# ciot.net
KiCad netlist of a schematic drawn in EAGLE
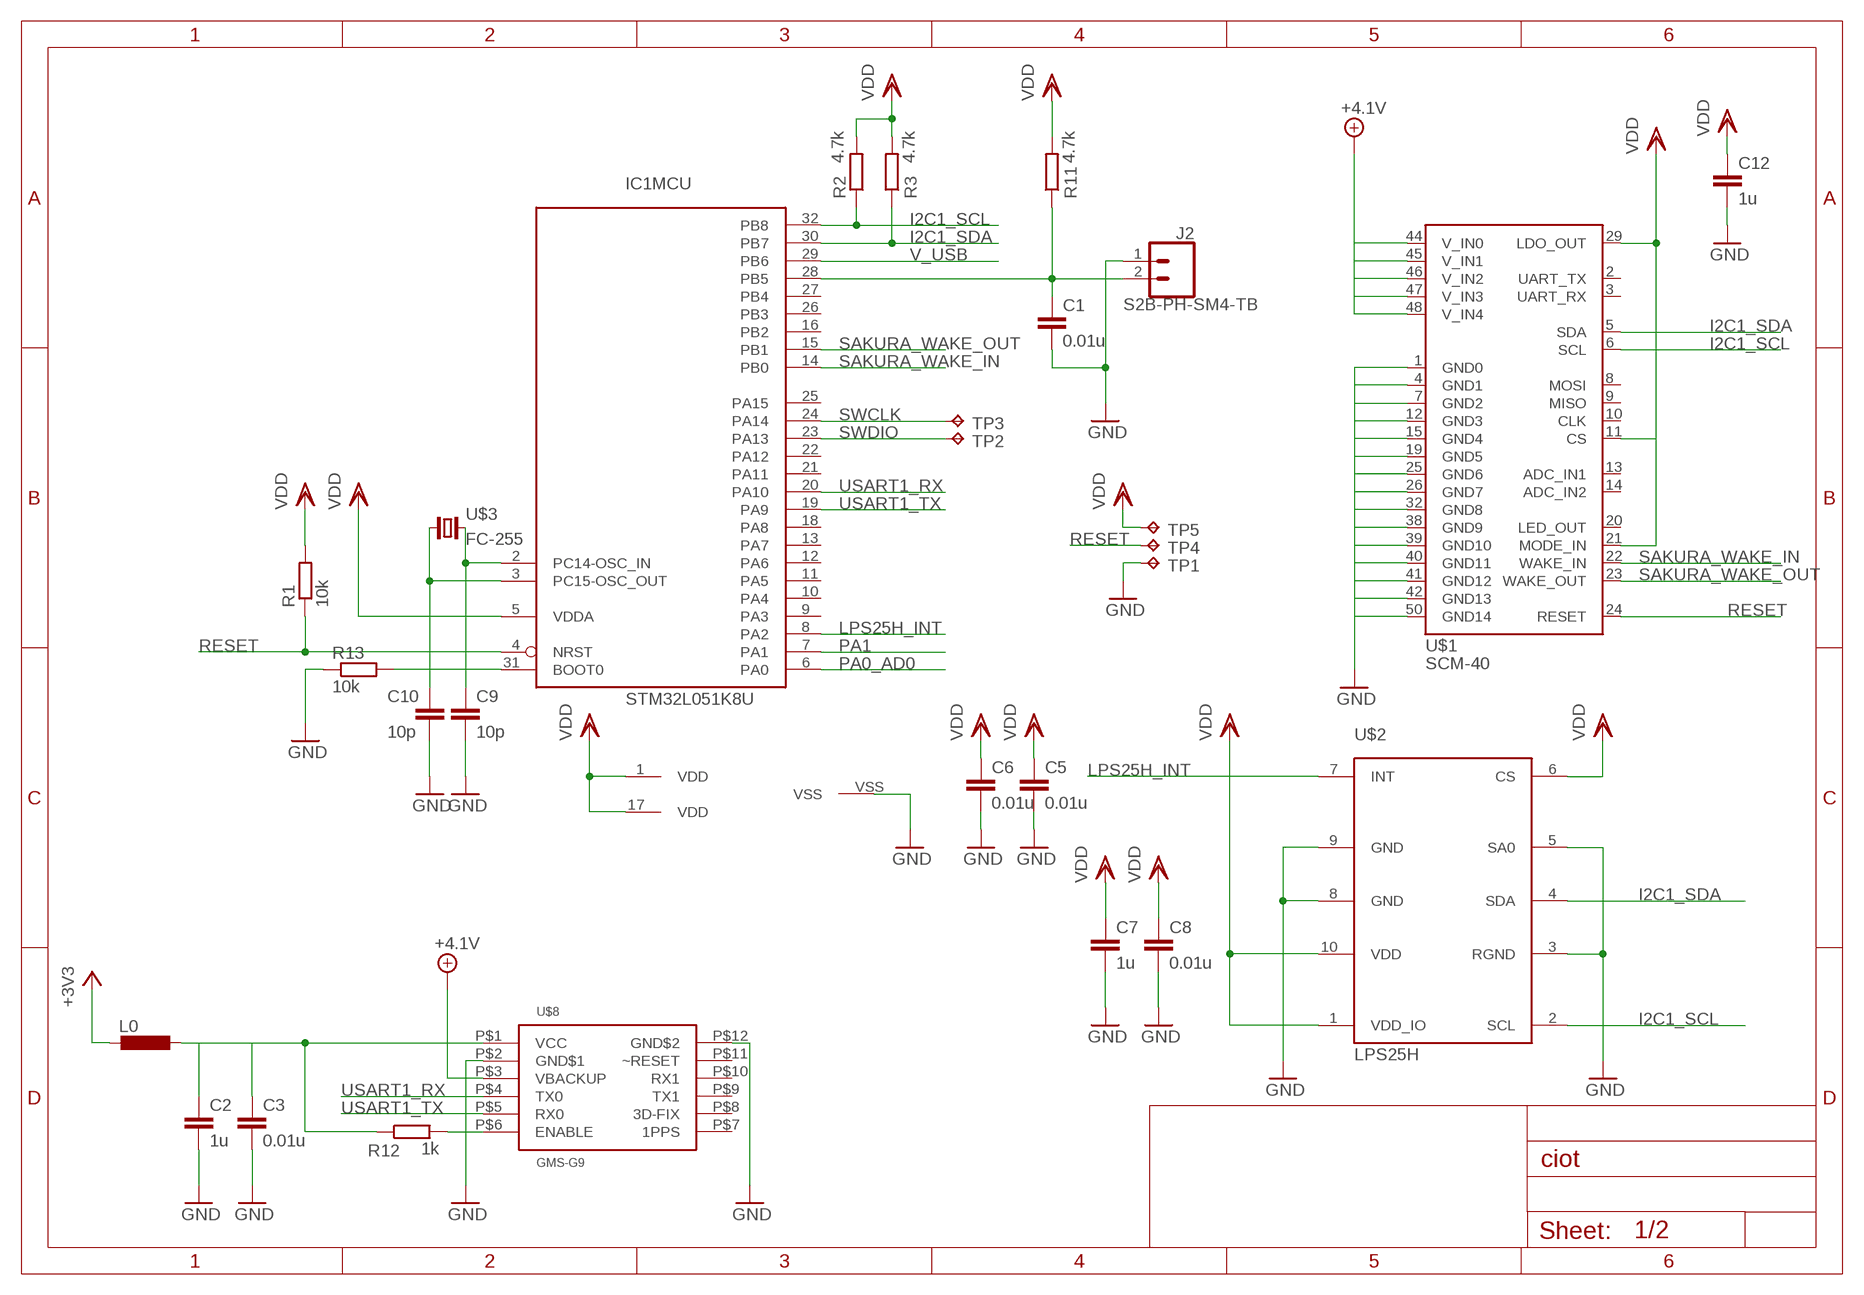
[diagram p0: schematic, sheet 1]
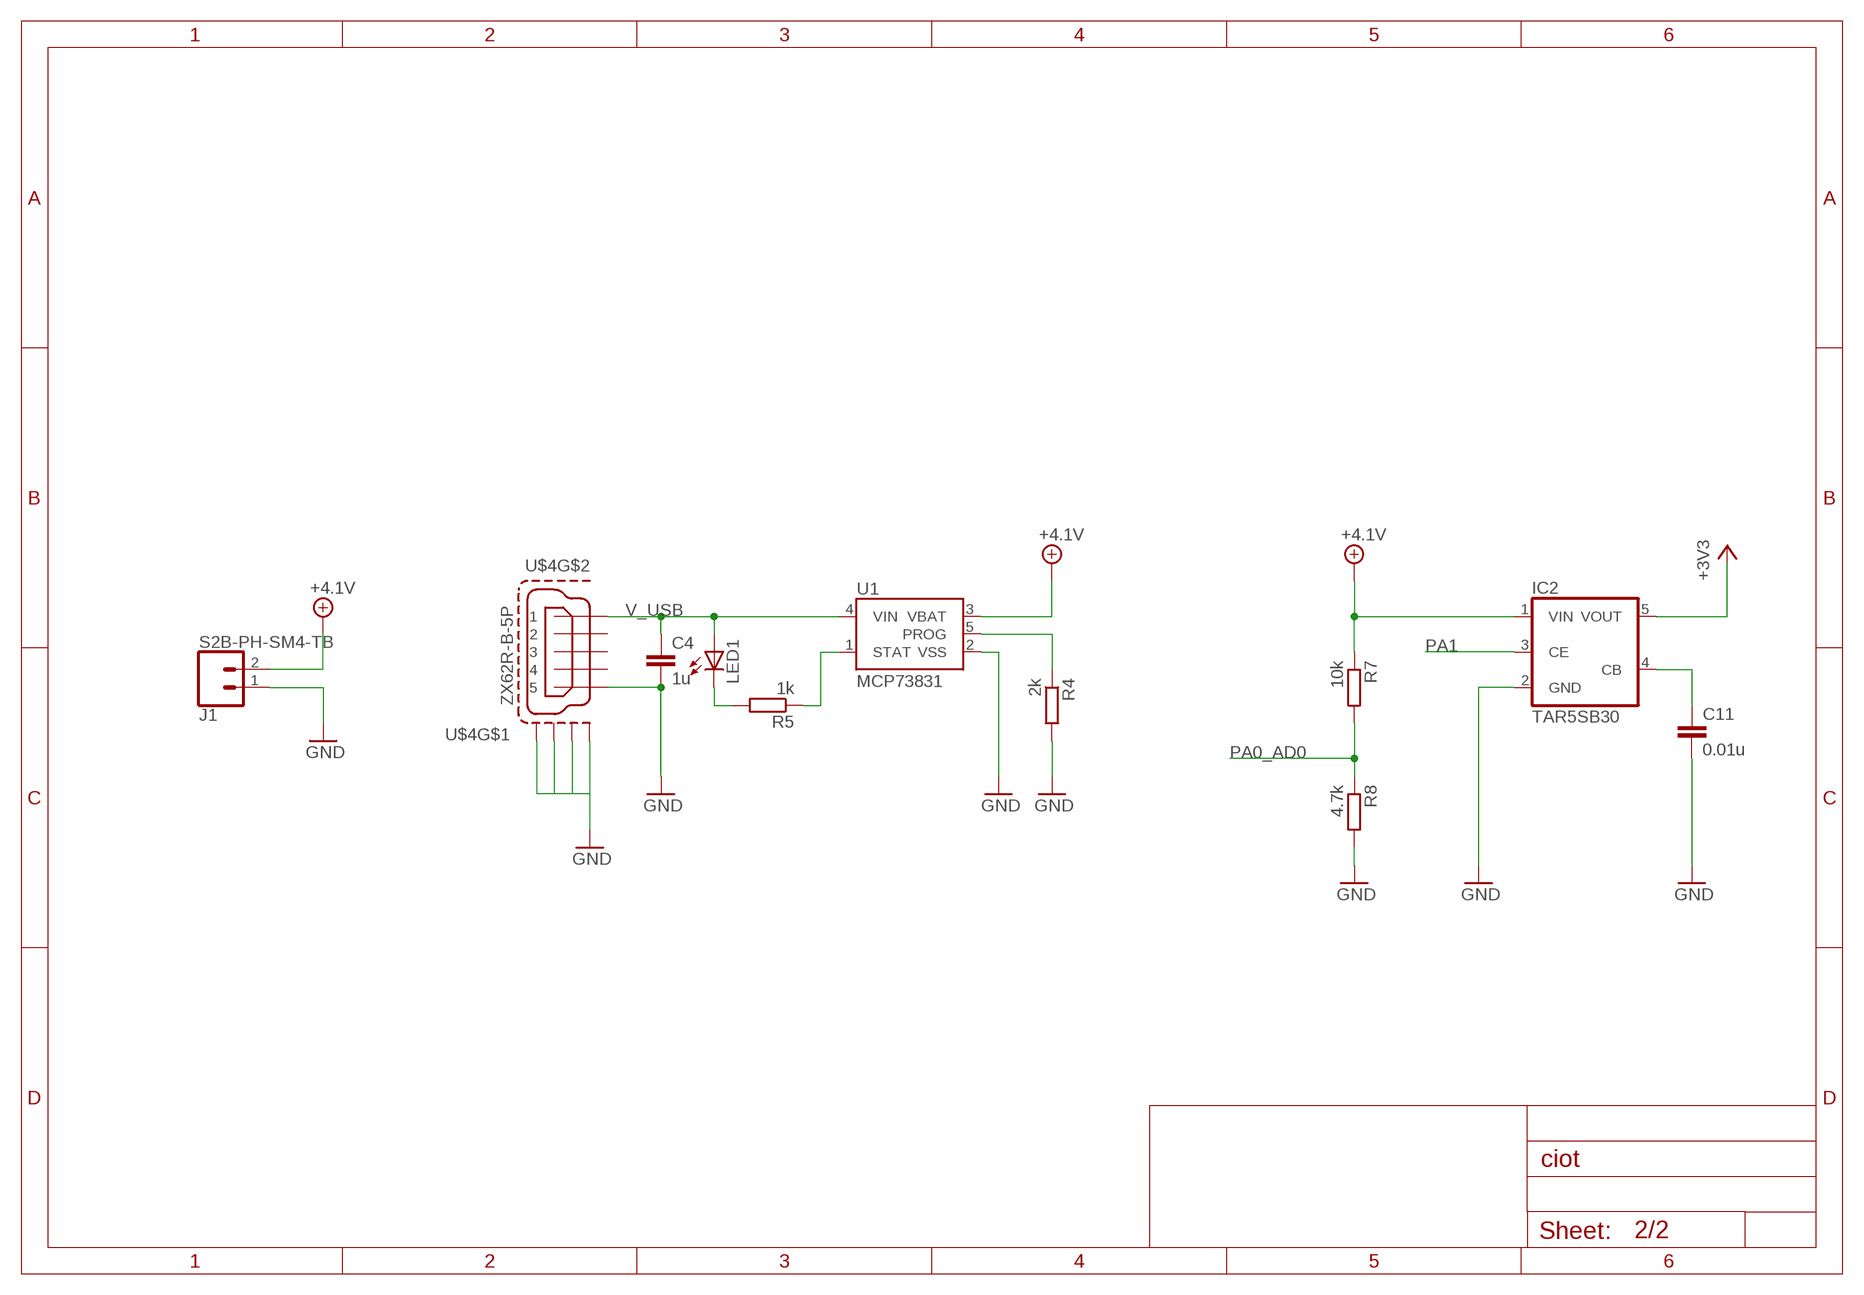
[diagram p1: schematic, sheet 2]

(export (version "E")
  (design (tool "Eeschema 10.0.6"))
  (components
    (comp (ref "C1")
      (value "0.01u")
      (footprint "eagle-import:C0603K")
      (libsource (lib "eagle-import") (part "C-EUC0603K"))
    )
    (comp (ref "C2")
      (value "1u")
      (footprint "eagle-import:C0603K")
      (libsource (lib "eagle-import") (part "C-EUC0603K"))
    )
    (comp (ref "C3")
      (value "0.01u")
      (footprint "eagle-import:C0603K")
      (libsource (lib "eagle-import") (part "C-EUC0603K"))
    )
    (comp (ref "C5")
      (value "0.01u")
      (footprint "eagle-import:C0603K")
      (libsource (lib "eagle-import") (part "C-EUC0603K"))
    )
    (comp (ref "C6")
      (value "0.01u")
      (footprint "eagle-import:C0603K")
      (libsource (lib "eagle-import") (part "C-EUC0603K"))
    )
    (comp (ref "C7")
      (value "1u")
      (footprint "eagle-import:C0603K")
      (libsource (lib "eagle-import") (part "C-EUC0603K"))
    )
    (comp (ref "C8")
      (value "0.01u")
      (footprint "eagle-import:C0603K")
      (libsource (lib "eagle-import") (part "C-EUC0603K"))
    )
    (comp (ref "C9")
      (value "10p")
      (footprint "eagle-import:C0603K")
      (libsource (lib "eagle-import") (part "C-EUC0603K"))
    )
    (comp (ref "C10")
      (value "10p")
      (footprint "eagle-import:C0603K")
      (libsource (lib "eagle-import") (part "C-EUC0603K"))
    )
    (comp (ref "C12")
      (value "1u")
      (footprint "eagle-import:C0603K")
      (libsource (lib "eagle-import") (part "C-EUC0603K"))
    )
    (comp (ref "IC1")
      (value "STM32L051K8U")
      (footprint "eagle-import:UFQFPN32")
      (libsource (lib "eagle-import") (part "STM32L051KU8"))
    )
    (comp (ref "J2")
      (value "S2B-PH-SM4-TB")
      (footprint "eagle-import:JST-2-SMD")
      (libsource (lib "eagle-import") (part "CONN_02-JST-2MM-SMT"))
    )
    (comp (ref "L0")
      (value "L-EUL2012C")
      (footprint "eagle-import:L2012C")
      (libsource (lib "eagle-import") (part "L-EUL2012C"))
    )
    (comp (ref "R1")
      (value "10k")
      (footprint "eagle-import:R0603")
      (libsource (lib "eagle-import") (part "R-EU_R0603"))
    )
    (comp (ref "R2")
      (value "4.7k")
      (footprint "eagle-import:R0603")
      (libsource (lib "eagle-import") (part "R-EU_R0603"))
    )
    (comp (ref "R3")
      (value "4.7k")
      (footprint "eagle-import:R0603")
      (libsource (lib "eagle-import") (part "R-EU_R0603"))
    )
    (comp (ref "R11")
      (value "4.7k")
      (footprint "eagle-import:R0603")
      (libsource (lib "eagle-import") (part "R-EU_R0603"))
    )
    (comp (ref "R12")
      (value "1k")
      (footprint "eagle-import:R0603")
      (libsource (lib "eagle-import") (part "R-EU_R0603"))
    )
    (comp (ref "R13")
      (value "10k")
      (footprint "eagle-import:R0603")
      (libsource (lib "eagle-import") (part "R-EU_R0603"))
    )
    (comp (ref "TP1")
      (value "TPB1,27")
      (footprint "eagle-import:B1,27")
      (libsource (lib "eagle-import") (part "TPB1,27"))
    )
    (comp (ref "TP2")
      (value "TPB1,27")
      (footprint "eagle-import:B1,27")
      (libsource (lib "eagle-import") (part "TPB1,27"))
    )
    (comp (ref "TP3")
      (value "TPB1,27")
      (footprint "eagle-import:B1,27")
      (libsource (lib "eagle-import") (part "TPB1,27"))
    )
    (comp (ref "TP4")
      (value "TPB1,27")
      (footprint "eagle-import:B1,27")
      (libsource (lib "eagle-import") (part "TPB1,27"))
    )
    (comp (ref "TP5")
      (value "TPB1,27")
      (footprint "eagle-import:B1,27")
      (libsource (lib "eagle-import") (part "TPB1,27"))
    )
    (comp (ref "U$1")
      (value "SCM-40")
      (footprint "eagle-import:SCM-DF40-50DS")
      (libsource (lib "eagle-import") (part "SCM-40"))
    )
    (comp (ref "U$2")
      (value "LPS25H")
      (footprint "eagle-import:LPS25H")
      (libsource (lib "eagle-import") (part "LPS25H"))
    )
    (comp (ref "U$3")
      (value "FC-255")
      (footprint "eagle-import:FC-255")
      (libsource (lib "eagle-import") (part "FC-255"))
    )
    (comp (ref "U$8")
      (value "GMS-G9")
      (footprint "eagle-import:GMS-G9")
      (libsource (lib "eagle-import") (part "GMS-G9"))
    )
    (comp (ref "C4")
      (value "1u")
      (footprint "eagle-import:C0603K")
      (libsource (lib "eagle-import") (part "C-EUC0603K"))
    )
    (comp (ref "C11")
      (value "0.01u")
      (footprint "eagle-import:C0603K")
      (libsource (lib "eagle-import") (part "C-EUC0603K"))
    )
    (comp (ref "IC2")
      (value "TAR5SB30")
      (footprint "eagle-import:SOT25")
      (libsource (lib "eagle-import") (part "TS520530"))
    )
    (comp (ref "J1")
      (value "S2B-PH-SM4-TB")
      (footprint "eagle-import:JST-2-SMD")
      (libsource (lib "eagle-import") (part "CONN_02-JST-2MM-SMT"))
    )
    (comp (ref "LED1")
      (value "LEDCHIPLED_0603")
      (footprint "eagle-import:CHIPLED_0603")
      (libsource (lib "eagle-import") (part "LEDCHIPLED_0603"))
    )
    (comp (ref "R4")
      (value "2k")
      (footprint "eagle-import:R0603")
      (libsource (lib "eagle-import") (part "R-EU_R0603"))
    )
    (comp (ref "R5")
      (value "1k")
      (footprint "eagle-import:R0603")
      (libsource (lib "eagle-import") (part "R-EU_R0603"))
    )
    (comp (ref "R7")
      (value "10k")
      (footprint "eagle-import:R0603")
      (libsource (lib "eagle-import") (part "R-EU_R0603"))
    )
    (comp (ref "R8")
      (value "4.7k")
      (footprint "eagle-import:R0603")
      (libsource (lib "eagle-import") (part "R-EU_R0603"))
    )
    (comp (ref "U$4")
      (value "ZX62R-B-5P")
      (footprint "eagle-import:ZX62R-B-5P")
      (libsource (lib "eagle-import") (part "MICRO-USB-SHIELD-ZX62R-B-5P"))
    )
    (comp (ref "U1")
      (value "MCP73831")
      (footprint "eagle-import:SOT23-5")
      (libsource (lib "eagle-import") (part "MCP73831"))
    )
  )
  (nets
    (net (code "1") (name "+3V3") (class "Default")
      (node (ref "IC2") (pin "5") (pinfunction "VOUT_5") (pintype "passive"))
      (node (ref "L0") (pin "2") (pinfunction "2_2") (pintype "passive"))
    )
    (net (code "2") (name "+4.1V") (class "Default")
      (node (ref "IC2") (pin "1") (pinfunction "VIN_1") (pintype "input"))
      (node (ref "J1") (pin "2") (pinfunction "1_2") (pintype "passive"))
      (node (ref "R7") (pin "1") (pinfunction "1_1") (pintype "passive"))
      (node (ref "U$1") (pin "44") (pinfunction "V_IN0_44") (pintype "power_in"))
      (node (ref "U$1") (pin "45") (pinfunction "V_IN1_45") (pintype "power_in"))
      (node (ref "U$1") (pin "46") (pinfunction "V_IN2_46") (pintype "power_in"))
      (node (ref "U$1") (pin "47") (pinfunction "V_IN3_47") (pintype "power_in"))
      (node (ref "U$1") (pin "48") (pinfunction "V_IN4_48") (pintype "power_in"))
      (node (ref "U$8") (pin "P$3") (pinfunction "VBACKUP_P$3") (pintype "bidirectional"))
      (node (ref "U1") (pin "3") (pinfunction "VBAT_3") (pintype "power_in"))
    )
    (net (code "3") (name "GND") (class "Default")
      (node (ref "C1") (pin "2") (pinfunction "2_2") (pintype "passive"))
      (node (ref "C10") (pin "2") (pinfunction "2_2") (pintype "passive"))
      (node (ref "C11") (pin "2") (pinfunction "2_2") (pintype "passive"))
      (node (ref "C12") (pin "2") (pinfunction "2_2") (pintype "passive"))
      (node (ref "C2") (pin "2") (pinfunction "2_2") (pintype "passive"))
      (node (ref "C3") (pin "2") (pinfunction "2_2") (pintype "passive"))
      (node (ref "C4") (pin "2") (pinfunction "2_2") (pintype "passive"))
      (node (ref "C5") (pin "2") (pinfunction "2_2") (pintype "passive"))
      (node (ref "C6") (pin "2") (pinfunction "2_2") (pintype "passive"))
      (node (ref "C7") (pin "2") (pinfunction "2_2") (pintype "passive"))
      (node (ref "C8") (pin "2") (pinfunction "2_2") (pintype "passive"))
      (node (ref "C9") (pin "2") (pinfunction "2_2") (pintype "passive"))
      (node (ref "IC1") (pin "VSS") (pinfunction "VSS_VSS") (pintype "power_in"))
      (node (ref "IC2") (pin "2") (pinfunction "GND_2") (pintype "passive"))
      (node (ref "J1") (pin "1") (pinfunction "2_1") (pintype "passive"))
      (node (ref "J2") (pin "1") (pinfunction "2_1") (pintype "passive"))
      (node (ref "R13") (pin "1") (pinfunction "1_1") (pintype "passive"))
      (node (ref "R4") (pin "2") (pinfunction "2_2") (pintype "passive"))
      (node (ref "R8") (pin "2") (pinfunction "2_2") (pintype "passive"))
      (node (ref "TP1") (pin "TP") (pinfunction "TP_TP") (pintype "input"))
      (node (ref "U$1") (pin "1") (pinfunction "GND0_1") (pintype "power_in"))
      (node (ref "U$1") (pin "12") (pinfunction "GND3_12") (pintype "power_in"))
      (node (ref "U$1") (pin "15") (pinfunction "GND4_15") (pintype "power_in"))
      (node (ref "U$1") (pin "19") (pinfunction "GND5_19") (pintype "power_in"))
      (node (ref "U$1") (pin "25") (pinfunction "GND6_25") (pintype "power_in"))
      (node (ref "U$1") (pin "26") (pinfunction "GND7_26") (pintype "power_in"))
      (node (ref "U$1") (pin "32") (pinfunction "GND8_32") (pintype "power_in"))
      (node (ref "U$1") (pin "38") (pinfunction "GND9_38") (pintype "power_in"))
      (node (ref "U$1") (pin "39") (pinfunction "GND10_39") (pintype "power_in"))
      (node (ref "U$1") (pin "4") (pinfunction "GND1_4") (pintype "power_in"))
      (node (ref "U$1") (pin "40") (pinfunction "GND11_40") (pintype "power_in"))
      (node (ref "U$1") (pin "41") (pinfunction "GND12_41") (pintype "power_in"))
      (node (ref "U$1") (pin "42") (pinfunction "GND13_42") (pintype "power_in"))
      (node (ref "U$1") (pin "50") (pinfunction "GND14_50") (pintype "power_in"))
      (node (ref "U$1") (pin "7") (pinfunction "GND2_7") (pintype "power_in"))
      (node (ref "U$2") (pin "3") (pinfunction "RGND_3") (pintype "bidirectional"))
      (node (ref "U$2") (pin "5") (pinfunction "SA0_5") (pintype "bidirectional"))
      (node (ref "U$2") (pin "8") (pinfunction "GND_8") (pintype "power_in"))
      (node (ref "U$2") (pin "9") (pinfunction "GND_9") (pintype "power_in"))
      (node (ref "U$4") (pin "5") (pinfunction "5_5") (pintype "input"))
      (node (ref "U$4") (pin "M1") (pinfunction "S1_M1") (pintype "passive"))
      (node (ref "U$4") (pin "M2") (pinfunction "S2_M2") (pintype "passive"))
      (node (ref "U$4") (pin "M3") (pinfunction "S3_M3") (pintype "passive"))
      (node (ref "U$4") (pin "M4") (pinfunction "S4_M4") (pintype "passive"))
      (node (ref "U$8") (pin "P$12") (pinfunction "GND$2_P$12") (pintype "bidirectional"))
      (node (ref "U$8") (pin "P$2") (pinfunction "GND$1_P$2") (pintype "bidirectional"))
      (node (ref "U1") (pin "2") (pinfunction "VSS_2") (pintype "power_in"))
    )
    (net (code "4") (name "I2C1_SCL") (class "Default")
      (node (ref "IC1") (pin "32") (pinfunction "PB8_32") (pintype "bidirectional"))
      (node (ref "R2") (pin "1") (pinfunction "1_1") (pintype "passive"))
      (node (ref "U$1") (pin "6") (pinfunction "SCL_6") (pintype "bidirectional"))
      (node (ref "U$2") (pin "2") (pinfunction "SCL_2") (pintype "bidirectional"))
    )
    (net (code "5") (name "I2C1_SDA") (class "Default")
      (node (ref "IC1") (pin "30") (pinfunction "PB7_30") (pintype "bidirectional"))
      (node (ref "R3") (pin "1") (pinfunction "1_1") (pintype "passive"))
      (node (ref "U$1") (pin "5") (pinfunction "SDA_5") (pintype "bidirectional"))
      (node (ref "U$2") (pin "4") (pinfunction "SDA_4") (pintype "bidirectional"))
    )
    (net (code "6") (name "LPS25H_INT") (class "Default")
      (node (ref "IC1") (pin "8") (pinfunction "PA2_8") (pintype "bidirectional"))
      (node (ref "U$2") (pin "7") (pinfunction "INT_7") (pintype "bidirectional"))
    )
    (net (code "7") (name "Net-(IC1A-BOOT0)") (class "Default")
      (node (ref "IC1") (pin "31") (pinfunction "BOOT0_31") (pintype "input"))
      (node (ref "R13") (pin "2") (pinfunction "2_2") (pintype "passive"))
    )
    (net (code "8") (name "Net-(IC1A-PB5)") (class "Default")
      (node (ref "C1") (pin "1") (pinfunction "1_1") (pintype "passive"))
      (node (ref "IC1") (pin "28") (pinfunction "PB5_28") (pintype "bidirectional"))
      (node (ref "J2") (pin "2") (pinfunction "1_2") (pintype "passive"))
      (node (ref "R11") (pin "1") (pinfunction "1_1") (pintype "passive"))
    )
    (net (code "9") (name "Net-(IC1A-PC14-OSC_IN)") (class "Default")
      (node (ref "C9") (pin "1") (pinfunction "1_1") (pintype "passive"))
      (node (ref "IC1") (pin "2") (pinfunction "PC14-OSC_IN_2") (pintype "bidirectional"))
      (node (ref "U$3") (pin "2") (pinfunction "2_2") (pintype "passive"))
    )
    (net (code "10") (name "Net-(IC1A-PC15-OSC_OUT)") (class "Default")
      (node (ref "C10") (pin "1") (pinfunction "1_1") (pintype "passive"))
      (node (ref "IC1") (pin "3") (pinfunction "PC15-OSC_OUT_3") (pintype "bidirectional"))
      (node (ref "U$3") (pin "1") (pinfunction "1_1") (pintype "passive"))
    )
    (net (code "11") (name "Net-(IC2-CB)") (class "Default")
      (node (ref "C11") (pin "1") (pinfunction "1_1") (pintype "passive"))
      (node (ref "IC2") (pin "4") (pinfunction "CB_4") (pintype "input"))
    )
    (net (code "12") (name "Net-(LED1-PadC)") (class "Default")
      (node (ref "LED1") (pin "C") (pinfunction "C_C") (pintype "passive"))
      (node (ref "R5") (pin "2") (pinfunction "2_2") (pintype "passive"))
    )
    (net (code "13") (name "Net-(U$8-ENABLE)") (class "Default")
      (node (ref "R12") (pin "2") (pinfunction "2_2") (pintype "passive"))
      (node (ref "U$8") (pin "P$6") (pinfunction "ENABLE_P$6") (pintype "bidirectional"))
    )
    (net (code "14") (name "Net-(U$8-VCC)") (class "Default")
      (node (ref "C2") (pin "1") (pinfunction "1_1") (pintype "passive"))
      (node (ref "C3") (pin "1") (pinfunction "1_1") (pintype "passive"))
      (node (ref "L0") (pin "1") (pinfunction "1_1") (pintype "passive"))
      (node (ref "R12") (pin "1") (pinfunction "1_1") (pintype "passive"))
      (node (ref "U$8") (pin "P$1") (pinfunction "VCC_P$1") (pintype "bidirectional"))
    )
    (net (code "15") (name "Net-(U1-PROG)") (class "Default")
      (node (ref "R4") (pin "1") (pinfunction "1_1") (pintype "passive"))
      (node (ref "U1") (pin "5") (pinfunction "PROG_5") (pintype "input"))
    )
    (net (code "16") (name "Net-(U1-STAT)") (class "Default")
      (node (ref "R5") (pin "1") (pinfunction "1_1") (pintype "passive"))
      (node (ref "U1") (pin "1") (pinfunction "STAT_1") (pintype "output"))
    )
    (net (code "17") (name "PA0_AD0") (class "Default")
      (node (ref "IC1") (pin "6") (pinfunction "PA0_6") (pintype "bidirectional"))
      (node (ref "R7") (pin "2") (pinfunction "2_2") (pintype "passive"))
      (node (ref "R8") (pin "1") (pinfunction "1_1") (pintype "passive"))
    )
    (net (code "18") (name "PA1") (class "Default")
      (node (ref "IC1") (pin "7") (pinfunction "PA1_7") (pintype "bidirectional"))
      (node (ref "IC2") (pin "3") (pinfunction "CE_3") (pintype "input"))
    )
    (net (code "19") (name "RESET") (class "Default")
      (node (ref "IC1") (pin "4") (pinfunction "NRST_4") (pintype "bidirectional"))
      (node (ref "R1") (pin "1") (pinfunction "1_1") (pintype "passive"))
      (node (ref "TP4") (pin "TP") (pinfunction "TP_TP") (pintype "input"))
      (node (ref "U$1") (pin "24") (pinfunction "RESET_24") (pintype "input"))
    )
    (net (code "20") (name "SAKURA_WAKE_IN") (class "Default")
      (node (ref "IC1") (pin "14") (pinfunction "PB0_14") (pintype "bidirectional"))
      (node (ref "U$1") (pin "22") (pinfunction "WAKE_IN_22") (pintype "input"))
    )
    (net (code "21") (name "SAKURA_WAKE_OUT") (class "Default")
      (node (ref "IC1") (pin "15") (pinfunction "PB1_15") (pintype "bidirectional"))
      (node (ref "U$1") (pin "23") (pinfunction "WAKE_OUT_23") (pintype "output"))
    )
    (net (code "22") (name "SWCLK") (class "Default")
      (node (ref "IC1") (pin "24") (pinfunction "PA14_24") (pintype "bidirectional"))
      (node (ref "TP3") (pin "TP") (pinfunction "TP_TP") (pintype "input"))
    )
    (net (code "23") (name "SWDIO") (class "Default")
      (node (ref "IC1") (pin "23") (pinfunction "PA13_23") (pintype "bidirectional"))
      (node (ref "TP2") (pin "TP") (pinfunction "TP_TP") (pintype "input"))
    )
    (net (code "24") (name "USART1_RX") (class "Default")
      (node (ref "IC1") (pin "20") (pinfunction "PA10_20") (pintype "bidirectional"))
      (node (ref "U$8") (pin "P$4") (pinfunction "TX0_P$4") (pintype "bidirectional"))
    )
    (net (code "25") (name "USART1_TX") (class "Default")
      (node (ref "IC1") (pin "19") (pinfunction "PA9_19") (pintype "bidirectional"))
      (node (ref "U$8") (pin "P$5") (pinfunction "RX0_P$5") (pintype "bidirectional"))
    )
    (net (code "26") (name "VDD") (class "Default")
      (node (ref "C12") (pin "1") (pinfunction "1_1") (pintype "passive"))
      (node (ref "C5") (pin "1") (pinfunction "1_1") (pintype "passive"))
      (node (ref "C6") (pin "1") (pinfunction "1_1") (pintype "passive"))
      (node (ref "C7") (pin "1") (pinfunction "1_1") (pintype "passive"))
      (node (ref "C8") (pin "1") (pinfunction "1_1") (pintype "passive"))
      (node (ref "IC1") (pin "1") (pinfunction "VDD_1") (pintype "power_in"))
      (node (ref "IC1") (pin "17") (pinfunction "VDD_17") (pintype "power_in"))
      (node (ref "IC1") (pin "5") (pinfunction "VDDA_5") (pintype "power_in"))
      (node (ref "R1") (pin "2") (pinfunction "2_2") (pintype "passive"))
      (node (ref "R11") (pin "2") (pinfunction "2_2") (pintype "passive"))
      (node (ref "R2") (pin "2") (pinfunction "2_2") (pintype "passive"))
      (node (ref "R3") (pin "2") (pinfunction "2_2") (pintype "passive"))
      (node (ref "TP5") (pin "TP") (pinfunction "TP_TP") (pintype "input"))
      (node (ref "U$1") (pin "11") (pinfunction "CS_11") (pintype "bidirectional"))
      (node (ref "U$1") (pin "21") (pinfunction "MODE_IN_21") (pintype "input"))
      (node (ref "U$1") (pin "29") (pinfunction "LDO_OUT_29") (pintype "power_in"))
      (node (ref "U$2") (pin "1") (pinfunction "VDD_IO_1") (pintype "power_in"))
      (node (ref "U$2") (pin "10") (pinfunction "VDD_10") (pintype "power_in"))
      (node (ref "U$2") (pin "6") (pinfunction "CS_6") (pintype "bidirectional"))
    )
    (net (code "27") (name "V_USB") (class "Default")
      (node (ref "C4") (pin "1") (pinfunction "1_1") (pintype "passive"))
      (node (ref "IC1") (pin "29") (pinfunction "PB6_29") (pintype "bidirectional"))
      (node (ref "LED1") (pin "A") (pinfunction "A_A") (pintype "passive"))
      (node (ref "U$4") (pin "1") (pinfunction "1_1") (pintype "input"))
      (node (ref "U1") (pin "4") (pinfunction "VIN_4") (pintype "power_in"))
    )
    (net (code "28") (name "unconnected-(IC1A-PA3-Pad9)") (class "Default")
      (node (ref "IC1") (pin "9") (pinfunction "PA3_9") (pintype "bidirectional"))
    )
    (net (code "29") (name "unconnected-(IC1A-PA4-Pad10)") (class "Default")
      (node (ref "IC1") (pin "10") (pinfunction "PA4_10") (pintype "bidirectional"))
    )
    (net (code "30") (name "unconnected-(IC1A-PA5-Pad11)") (class "Default")
      (node (ref "IC1") (pin "11") (pinfunction "PA5_11") (pintype "bidirectional"))
    )
    (net (code "31") (name "unconnected-(IC1A-PA6-Pad12)") (class "Default")
      (node (ref "IC1") (pin "12") (pinfunction "PA6_12") (pintype "bidirectional"))
    )
    (net (code "32") (name "unconnected-(IC1A-PA7-Pad13)") (class "Default")
      (node (ref "IC1") (pin "13") (pinfunction "PA7_13") (pintype "bidirectional"))
    )
    (net (code "33") (name "unconnected-(IC1A-PA8-Pad18)") (class "Default")
      (node (ref "IC1") (pin "18") (pinfunction "PA8_18") (pintype "bidirectional"))
    )
    (net (code "34") (name "unconnected-(IC1A-PA11-Pad21)") (class "Default")
      (node (ref "IC1") (pin "21") (pinfunction "PA11_21") (pintype "bidirectional"))
    )
    (net (code "35") (name "unconnected-(IC1A-PA12-Pad22)") (class "Default")
      (node (ref "IC1") (pin "22") (pinfunction "PA12_22") (pintype "bidirectional"))
    )
    (net (code "36") (name "unconnected-(IC1A-PA15-Pad25)") (class "Default")
      (node (ref "IC1") (pin "25") (pinfunction "PA15_25") (pintype "bidirectional"))
    )
    (net (code "37") (name "unconnected-(IC1A-PB2-Pad16)") (class "Default")
      (node (ref "IC1") (pin "16") (pinfunction "PB2_16") (pintype "bidirectional"))
    )
    (net (code "38") (name "unconnected-(IC1A-PB3-Pad26)") (class "Default")
      (node (ref "IC1") (pin "26") (pinfunction "PB3_26") (pintype "bidirectional"))
    )
    (net (code "39") (name "unconnected-(IC1A-PB4-Pad27)") (class "Default")
      (node (ref "IC1") (pin "27") (pinfunction "PB4_27") (pintype "bidirectional"))
    )
    (net (code "40") (name "unconnected-(U$1-ADC_IN1-Pad13)") (class "Default")
      (node (ref "U$1") (pin "13") (pinfunction "ADC_IN1_13") (pintype "input"))
    )
    (net (code "41") (name "unconnected-(U$1-ADC_IN2-Pad14)") (class "Default")
      (node (ref "U$1") (pin "14") (pinfunction "ADC_IN2_14") (pintype "input"))
    )
    (net (code "42") (name "unconnected-(U$1-CLK-Pad10)") (class "Default")
      (node (ref "U$1") (pin "10") (pinfunction "CLK_10") (pintype "bidirectional"))
    )
    (net (code "43") (name "unconnected-(U$1-LED_OUT-Pad20)") (class "Default")
      (node (ref "U$1") (pin "20") (pinfunction "LED_OUT_20") (pintype "output"))
    )
    (net (code "44") (name "unconnected-(U$1-MISO-Pad9)") (class "Default")
      (node (ref "U$1") (pin "9") (pinfunction "MISO_9") (pintype "bidirectional"))
    )
    (net (code "45") (name "unconnected-(U$1-MOSI-Pad8)") (class "Default")
      (node (ref "U$1") (pin "8") (pinfunction "MOSI_8") (pintype "bidirectional"))
    )
    (net (code "46") (name "unconnected-(U$1-UART_RX-Pad3)") (class "Default")
      (node (ref "U$1") (pin "3") (pinfunction "UART_RX_3") (pintype "input"))
    )
    (net (code "47") (name "unconnected-(U$1-UART_TX-Pad2)") (class "Default")
      (node (ref "U$1") (pin "2") (pinfunction "UART_TX_2") (pintype "output"))
    )
    (net (code "48") (name "unconnected-(U$4-Pad2)") (class "Default")
      (node (ref "U$4") (pin "2") (pinfunction "2_2") (pintype "input"))
    )
    (net (code "49") (name "unconnected-(U$4-Pad3)") (class "Default")
      (node (ref "U$4") (pin "3") (pinfunction "3_3") (pintype "input"))
    )
    (net (code "50") (name "unconnected-(U$4-Pad4)") (class "Default")
      (node (ref "U$4") (pin "4") (pinfunction "4_4") (pintype "input"))
    )
    (net (code "51") (name "unconnected-(U$8-1PPS-PadP$7)") (class "Default")
      (node (ref "U$8") (pin "P$7") (pinfunction "1PPS_P$7") (pintype "bidirectional"))
    )
    (net (code "52") (name "unconnected-(U$8-3D-FIX-PadP$8)") (class "Default")
      (node (ref "U$8") (pin "P$8") (pinfunction "3D-FIX_P$8") (pintype "bidirectional"))
    )
    (net (code "53") (name "unconnected-(U$8-RX1-PadP$10)") (class "Default")
      (node (ref "U$8") (pin "P$10") (pinfunction "RX1_P$10") (pintype "bidirectional"))
    )
    (net (code "54") (name "unconnected-(U$8-TX1-PadP$9)") (class "Default")
      (node (ref "U$8") (pin "P$9") (pinfunction "TX1_P$9") (pintype "bidirectional"))
    )
    (net (code "55") (name "unconnected-(U$8-~{RESET}-PadP$11)") (class "Default")
      (node (ref "U$8") (pin "P$11") (pinfunction "~{RESET}_P$11") (pintype "bidirectional"))
    )
  )
)
